# Sheet2.net
KiCad netlist of a schematic drawn in Altium Designer
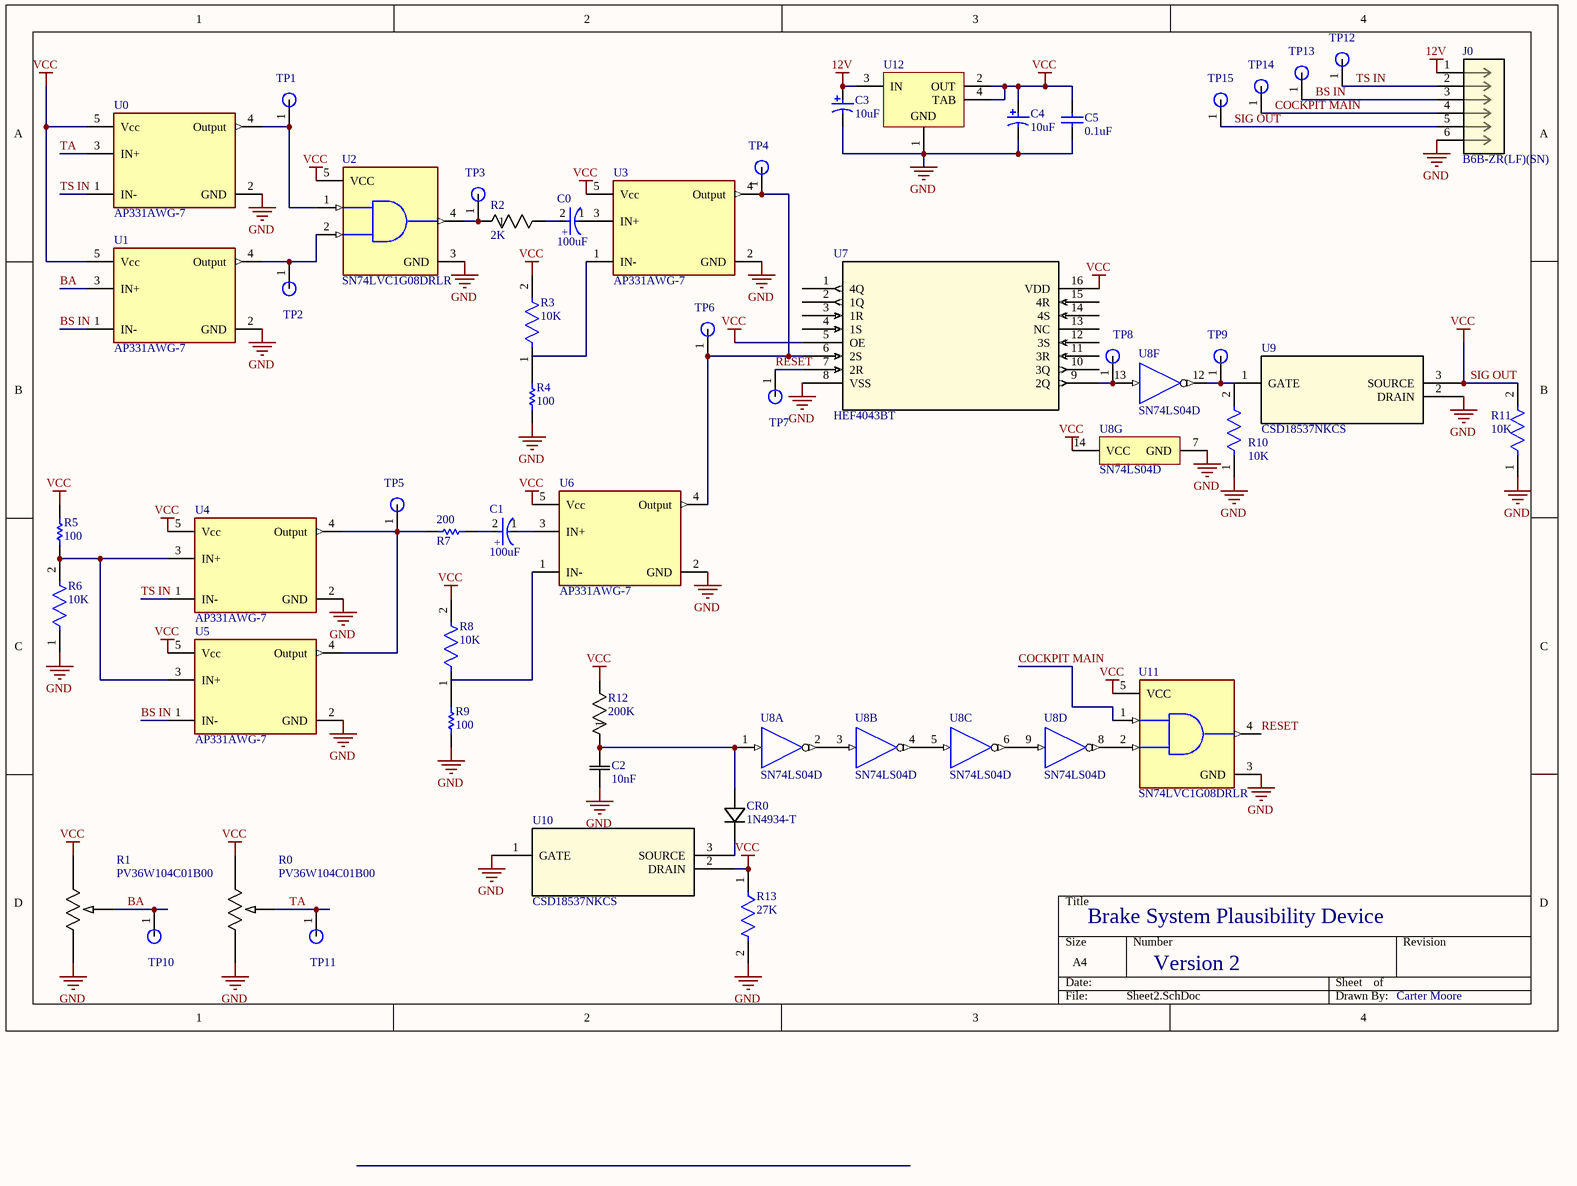
[diagram p0: Sheet2.SchDoc]

(export (version "E")
  (design (tool "Eeschema 10.0.6"))
  (components
    (comp (ref "200")
      (value "R7")
      (footprint "RESC0603X28X15ML05T05")
      (fields (field (name "MANUFACTURER") "Vishay Dale") (field (name "PART NUMBER") "CRCW0201200RJNED"))
      (libsource (lib "Schlib2") (part "RES"))
    )
    (comp (ref "C0")
      (value "100uF")
      (footprint "FP-MAL2150-1010-MFG")
      (description "CAP ALUM 100UF 20% 50V SMD")
      (fields (field (name "TOLERANCE") "20%"))
      (libsource (lib "Schlib2") (part "203bc49f2ac43e59fd269a8c329ed05"))
    )
    (comp (ref "C1")
      (value "100uF")
      (footprint "FP-MAL2150-1010-MFG")
      (description "CAP ALUM 100UF 20% 50V SMD")
      (fields (field (name "TOLERANCE") "20%"))
      (libsource (lib "Schlib2") (part "203bc49f2ac43e59fd269a8c329ed05"))
    )
    (comp (ref "C2")
      (value "10nF")
      (footprint "CAP_C317C_MR_X7R_KEM")
      (description "CAP CER 10000PF 50V X7R RADIAL")
      (fields
        (field (name "MANUFACTURER_PART_NUMBER") "C317C103K5R5TA")
        (field (name "COPYRIGHT") "Copyright (C) 2023 Ultra Librarian. All rights reserved.")
      )
      (libsource (lib "Schlib2") (part "C317C103K5R5TA"))
    )
    (comp (ref "C3")
      (value "10uF")
      (footprint "PNSC-EEU-EE2G100-2_V")
      (fields (field (name "PARTNUMBER") "EEU-EE2G100") (field (name "MANUFACTURER") "Panasonic"))
      (libsource (lib "Altium Content Vault") (part "PNSC-CAP-P-2"))
    )
    (comp (ref "C4")
      (value "10uF")
      (footprint "PNSC-EEU-EE2G100-2_V")
      (fields (field (name "PARTNUMBER") "EEU-EE2G100") (field (name "MANUFACTURER") "Panasonic"))
      (libsource (lib "Altium Content Vault") (part "PNSC-CAP-P-2"))
    )
    (comp (ref "C5")
      (value "0.1uF")
      (footprint "AVX-SA115C104KAR")
      (fields (field (name "TOLERANCE") "±10%") (field (name "MANUFACTURER") "AVX"))
      (libsource (lib "Altium Content Vault") (part "CAP-NP-2"))
    )
    (comp (ref "CR0")
      (value "1N4934-T")
      (footprint "DO-41_DIO")
      (description "No Description Available")
      (fields (field (name "COPYRIGHT") "Copyright (C) 2023 Ultra Librarian. All rights reserved."))
      (libsource (lib "Schlib2") (part "1N4934-T"))
    )
    (comp (ref "J0")
      (value "B6B-ZR(LF)(SN)")
      (footprint "CONN_B6B-ZR_JST")
      (description "CONN HEADER VERT 6POS 1.5MM")
      (fields (field (name "COPYRIGHT") "Copyright (C) 2023 Ultra Librarian. All rights reserved."))
      (libsource (lib "Schlib2") (part "B6B-ZRLFSN"))
    )
    (comp (ref "R0")
      (value "PV36W104C01B00")
      (footprint "POT_PV36W_BRN")
      (description "TRIMMER 100K OHM 0.5W PC PIN TOP")
      (libsource (lib "Schlib2") (part "PV36W104C01B00"))
    )
    (comp (ref "R1")
      (value "PV36W104C01B00")
      (footprint "POT_PV36W_BRN")
      (description "TRIMMER 100K OHM 0.5W PC PIN TOP")
      (libsource (lib "Schlib2") (part "PV36W104C01B00"))
    )
    (comp (ref "R2")
      (value "2K")
      (footprint "YAG_MF25_YAG")
      (description "No Description Available")
      (fields
        (field (name "MANUFACTURER_PART_NUMBER") "MFR-25FRF52-2K")
        (field (name "COPYRIGHT") "Copyright (C) 2023 Ultra Librarian. All rights reserved.")
      )
      (libsource (lib "Schlib2") (part "MFR-25FRF52-2K"))
    )
    (comp (ref "R3")
      (value "10K")
      (footprint "FP-MF0207-MFG")
      (description "RES 10K OHM 1% 0.6W AXIAL")
      (fields (field (name "TOLERANCE") "1%"))
      (libsource (lib "Altium Content Vault") (part "1029c3af85768c4190bb7ad29bc67b5"))
    )
    (comp (ref "R4")
      (value "100")
      (footprint "RESA60-630X240")
      (description "Axial Resistor, 100 Ohm, +/- 1%, 0.25 W, -55 to 155 degC, 2-Pin THD, RoHS, Bulk")
      (fields (field (name "TOLERANCE") "1%"))
      (libsource (lib "Altium Content Vault") (part "RES-2"))
    )
    (comp (ref "R5")
      (value "100")
      (footprint "RESA60-630X240")
      (description "Axial Resistor, 100 Ohm, +/- 1%, 0.25 W, -55 to 155 degC, 2-Pin THD, RoHS, Bulk")
      (fields (field (name "TOLERANCE") "1%"))
      (libsource (lib "Schlib2") (part "RES-2"))
    )
    (comp (ref "R6")
      (value "10K")
      (footprint "FP-MF0207-MFG")
      (description "RES 10K OHM 1% 0.6W AXIAL")
      (fields (field (name "TOLERANCE") "1%"))
      (libsource (lib "Schlib2") (part "1029c3af85768c4190bb7ad29bc67b5"))
    )
    (comp (ref "R8")
      (value "10K")
      (footprint "FP-MF0207-MFG")
      (description "RES 10K OHM 1% 0.6W AXIAL")
      (fields (field (name "TOLERANCE") "1%"))
      (libsource (lib "Altium Content Vault") (part "1029c3af85768c4190bb7ad29bc67b5"))
    )
    (comp (ref "R9")
      (value "100")
      (footprint "RESA60-630X240")
      (description "Axial Resistor, 100 Ohm, +/- 1%, 0.25 W, -55 to 155 degC, 2-Pin THD, RoHS, Bulk")
      (fields (field (name "TOLERANCE") "1%"))
      (libsource (lib "Altium Content Vault") (part "RES-2"))
    )
    (comp (ref "R10")
      (value "10K")
      (footprint "FP-MF0207-MFG")
      (description "RES 10K OHM 1% 0.6W AXIAL")
      (fields (field (name "TOLERANCE") "1%"))
      (libsource (lib "Schlib2") (part "1029c3af85768c4190bb7ad29bc67b5"))
    )
    (comp (ref "R11")
      (value "10K")
      (footprint "FP-MF0207-MFG")
      (description "RES 10K OHM 1% 0.6W AXIAL")
      (fields (field (name "TOLERANCE") "1%"))
      (libsource (lib "Schlib2") (part "1029c3af85768c4190bb7ad29bc67b5"))
    )
    (comp (ref "R12")
      (value "200K")
      (footprint "YAG_MF25_YAG")
      (description "RES 200K OHM 1% 1/4W AXIAL")
      (fields
        (field (name "MANUFACTURER_PART_NUMBER") "MFR-25FRF52-200K")
        (field (name "COPYRIGHT") "Copyright (C) 2023 Ultra Librarian. All rights reserved.")
      )
      (libsource (lib "Schlib2") (part "MFR-25FRF52-200K"))
    )
    (comp (ref "R13")
      (value "27K")
      (footprint "FP-RT0402-MFG")
      (description "RES SMD 27K OHM 0.5% 1/16W 0402")
      (fields
        (field (name "MANUFACTURER") "Yageo")
        (field (name "MANUFACTURER PART NUMBER") "RT0402DRE0727KL")
      )
      (libsource (lib "Altium Content Vault") (part "1029c3af85768c4190bb7ad29bc67b5"))
    )
    (comp (ref "TP1") (value "Test Point") (footprint "TP1") (libsource (lib "Schlib2") (part "Test Point")))
    (comp (ref "TP2") (value "Test Point") (footprint "TP1") (libsource (lib "Schlib2") (part "Test Point")))
    (comp (ref "TP3") (value "Test Point") (footprint "TP1") (libsource (lib "Schlib2") (part "Test Point")))
    (comp (ref "TP4") (value "Test Point") (footprint "TP1") (libsource (lib "Schlib2") (part "Test Point")))
    (comp (ref "TP5") (value "Test Point") (footprint "TP1") (libsource (lib "Schlib2") (part "Test Point")))
    (comp (ref "TP6") (value "Test Point") (footprint "TP1") (libsource (lib "Schlib2") (part "Test Point")))
    (comp (ref "TP7") (value "Test Point") (footprint "TP1") (libsource (lib "Schlib2") (part "Test Point")))
    (comp (ref "TP8") (value "Test Point") (footprint "TP1") (libsource (lib "Schlib2") (part "Test Point")))
    (comp (ref "TP9") (value "Test Point") (footprint "TP1") (libsource (lib "Schlib2") (part "Test Point")))
    (comp (ref "TP10") (value "Test Point") (footprint "TP1") (libsource (lib "Schlib2") (part "Test Point")))
    (comp (ref "TP11") (value "Test Point") (footprint "TP1") (libsource (lib "Schlib2") (part "Test Point")))
    (comp (ref "TP12") (value "Test Point") (footprint "TP1") (libsource (lib "Schlib2") (part "Test Point")))
    (comp (ref "TP13") (value "Test Point") (footprint "TP1") (libsource (lib "Schlib2") (part "Test Point")))
    (comp (ref "TP14") (value "Test Point") (footprint "TP1") (libsource (lib "Schlib2") (part "Test Point")))
    (comp (ref "TP15") (value "Test Point") (footprint "TP1") (libsource (lib "Schlib2") (part "Test Point")))
    (comp (ref "U0")
      (value "AP331AWG-7")
      (footprint "FP-SOT25-MFG")
      (description "IC COMPARATOR SGL DIFF SOT-25")
      (fields
        (field (name "MANUFACTURER") "Diodes Inc.")
        (field (name "OCTOPART") "https://octopart.com/ap331awg-7-diodes+inc.-12688108")
      )
      (libsource (lib "Schlib2") (part "84157f6d693ce6938d681314262b7f3"))
    )
    (comp (ref "U1")
      (value "AP331AWG-7")
      (footprint "FP-SOT25-MFG")
      (description "IC COMPARATOR SGL DIFF SOT-25")
      (fields
        (field (name "MANUFACTURER") "Diodes Inc.")
        (field (name "OCTOPART") "https://octopart.com/ap331awg-7-diodes+inc.-12688108")
      )
      (libsource (lib "Schlib2") (part "84157f6d693ce6938d681314262b7f3"))
    )
    (comp (ref "U2")
      (value "SN74LVC1G08DRLR")
      (footprint "FP-DRL0005A-MFG")
      (description "IC GATE AND 1CH 2-INP SOT5")
      (fields
        (field (name "MANUFACTURER") "Texas Instruments")
        (field (name "OCTOPART") "https://octopart.com/sn74lvc1g08drlr-texas+instruments-464956")
      )
      (libsource (lib "Schlib2") (part "cbd873ac6525a059c6951788f409ef0"))
    )
    (comp (ref "U3")
      (value "AP331AWG-7")
      (footprint "FP-SOT25-MFG")
      (description "IC COMPARATOR SGL DIFF SOT-25")
      (fields
        (field (name "MANUFACTURER") "Diodes Inc.")
        (field (name "OCTOPART") "https://octopart.com/ap331awg-7-diodes+inc.-12688108")
      )
      (libsource (lib "Schlib2") (part "84157f6d693ce6938d681314262b7f3"))
    )
    (comp (ref "U4")
      (value "AP331AWG-7")
      (footprint "FP-SOT25-MFG")
      (description "IC COMPARATOR SGL DIFF SOT-25")
      (fields
        (field (name "MANUFACTURER") "Diodes Inc.")
        (field (name "OCTOPART") "https://octopart.com/ap331awg-7-diodes+inc.-12688108")
      )
      (libsource (lib "Schlib2") (part "84157f6d693ce6938d681314262b7f3"))
    )
    (comp (ref "U5")
      (value "AP331AWG-7")
      (footprint "FP-SOT25-MFG")
      (description "IC COMPARATOR SGL DIFF SOT-25")
      (fields
        (field (name "MANUFACTURER") "Diodes Inc.")
        (field (name "OCTOPART") "https://octopart.com/ap331awg-7-diodes+inc.-12688108")
      )
      (libsource (lib "Schlib2") (part "84157f6d693ce6938d681314262b7f3"))
    )
    (comp (ref "U6")
      (value "AP331AWG-7")
      (footprint "FP-SOT25-MFG")
      (description "IC COMPARATOR SGL DIFF SOT-25")
      (fields
        (field (name "MANUFACTURER") "Diodes Inc.")
        (field (name "OCTOPART") "https://octopart.com/ap331awg-7-diodes+inc.-12688108")
      )
      (libsource (lib "Schlib2") (part "84157f6d693ce6938d681314262b7f3"))
    )
    (comp (ref "U7")
      (value "HEF4043BT")
      (footprint "SOT109-1_NXP")
      (description "IC R/S LATCH 3-STATE QUAD 16SOIC")
      (fields (field (name "COPYRIGHT") "Copyright (C) 2023 Ultra Librarian. All rights reserved."))
      (libsource (lib "Schlib2") (part "HEF4043BT"))
    )
    (comp (ref "U8")
      (value "SN74LS04D")
      (footprint "D0014A_N")
      (description "Hex inverters, D0014A, TUBE")
      (fields
        (field (name "GENERIC PART NUMBER") "SN74LS04")
        (field (name "MANUFACTURER") "Texas Instruments")
      )
      (libsource (lib "Schlib2") (part "TI-CD_SNX4XXXXXX4X_19A-14"))
    )
    (comp (ref "U9")
      (value "CSD18537NKCS")
      (footprint "KCS3_TEX")
      (description "No Description Available")
      (fields (field (name "COPYRIGHT") "Copyright (C) 2023 Ultra Librarian. All rights reserved."))
      (libsource (lib "Schlib2") (part "CSD18537NKCS"))
    )
    (comp (ref "U10")
      (value "CSD18537NKCS")
      (footprint "KCS3_TEX")
      (description "No Description Available")
      (fields (field (name "COPYRIGHT") "Copyright (C) 2023 Ultra Librarian. All rights reserved."))
      (libsource (lib "Schlib2") (part "CSD18537NKCS"))
    )
    (comp (ref "U11")
      (value "SN74LVC1G08DRLR")
      (footprint "FP-DRL0005A-MFG")
      (description "IC GATE AND 1CH 2-INP SOT5")
      (fields
        (field (name "MANUFACTURER") "Texas Instruments")
        (field (name "OCTOPART") "https://octopart.com/sn74lvc1g08drlr-texas+instruments-464956")
      )
      (libsource (lib "Schlib2") (part "cbd873ac6525a059c6951788f409ef0"))
    )
    (comp (ref "U12")
      (value "LM1117MPX-5.0/NOPB")
      (footprint "DCY0004A_L")
      (description "800mA Low-Dropout Linear Regulator, 4-pin SOT-223, Pb-Free")
      (fields (field (name "MANUFACTURER") "Texas Instruments"))
      (libsource (lib "Altium Content Vault") (part "PM-REG-LM1086-SOT4"))
    )
  )
  (nets
    (net (code "1") (name "/BA") (class "Default")
      (node (ref "R1") (pin "2") (pinfunction "2_2") (pintype "passive"))
      (node (ref "TP10") (pin "1") (pinfunction "1_1") (pintype "passive"))
      (node (ref "U1") (pin "3") (pinfunction "IN+_3") (pintype "tri_state"))
    )
    (net (code "2") (name "/BS IN") (class "Default")
      (node (ref "J0") (pin "3") (pinfunction "3_3") (pintype "passive"))
      (node (ref "TP13") (pin "1") (pinfunction "1_1") (pintype "passive"))
      (node (ref "U1") (pin "1") (pinfunction "IN-_1") (pintype "tri_state"))
      (node (ref "U5") (pin "1") (pinfunction "IN-_1") (pintype "tri_state"))
    )
    (net (code "3") (name "/COCKPIT MAIN") (class "Default")
      (node (ref "J0") (pin "4") (pinfunction "4_4") (pintype "passive"))
      (node (ref "TP14") (pin "1") (pinfunction "1_1") (pintype "passive"))
      (node (ref "U11") (pin "1") (pinfunction "A_1") (pintype "input"))
    )
    (net (code "4") (name "/RESET") (class "Default")
      (node (ref "TP7") (pin "1") (pinfunction "1_1") (pintype "passive"))
      (node (ref "U11") (pin "4") (pinfunction "Y_4") (pintype "output"))
      (node (ref "U7") (pin "7") (pinfunction "2R_7") (pintype "input"))
    )
    (net (code "5") (name "/TA") (class "Default")
      (node (ref "R0") (pin "2") (pinfunction "2_2") (pintype "passive"))
      (node (ref "TP11") (pin "1") (pinfunction "1_1") (pintype "passive"))
      (node (ref "U0") (pin "3") (pinfunction "IN+_3") (pintype "tri_state"))
    )
    (net (code "6") (name "/TS IN") (class "Default")
      (node (ref "J0") (pin "2") (pinfunction "2_2") (pintype "passive"))
      (node (ref "TP12") (pin "1") (pinfunction "1_1") (pintype "passive"))
      (node (ref "U0") (pin "1") (pinfunction "IN-_1") (pintype "tri_state"))
      (node (ref "U4") (pin "1") (pinfunction "IN-_1") (pintype "tri_state"))
    )
    (net (code "7") (name "12V") (class "Default")
      (node (ref "C3") (pin "1") (pinfunction "1_1") (pintype "passive"))
      (node (ref "J0") (pin "1") (pinfunction "1_1") (pintype "passive"))
      (node (ref "U12") (pin "3") (pinfunction "IN_3") (pintype "power_in"))
    )
    (net (code "8") (name "GND") (class "Default")
      (node (ref "C2") (pin "1") (pinfunction "1_1") (pintype "passive"))
      (node (ref "C3") (pin "2") (pinfunction "2_2") (pintype "passive"))
      (node (ref "C4") (pin "2") (pinfunction "2_2") (pintype "passive"))
      (node (ref "C5") (pin "1") (pinfunction "1_1") (pintype "passive"))
      (node (ref "J0") (pin "6") (pinfunction "6_6") (pintype "passive"))
      (node (ref "R0") (pin "3") (pinfunction "3_3") (pintype "passive"))
      (node (ref "R1") (pin "3") (pinfunction "3_3") (pintype "passive"))
      (node (ref "R10") (pin "1") (pinfunction "1_1") (pintype "passive"))
      (node (ref "R11") (pin "1") (pinfunction "1_1") (pintype "passive"))
      (node (ref "R13") (pin "2") (pinfunction "2_2") (pintype "passive"))
      (node (ref "R4") (pin "1") (pinfunction "1_1") (pintype "passive"))
      (node (ref "R6") (pin "1") (pinfunction "1_1") (pintype "passive"))
      (node (ref "R9") (pin "1") (pinfunction "1_1") (pintype "passive"))
      (node (ref "U0") (pin "2") (pinfunction "GND_2") (pintype "power_in"))
      (node (ref "U1") (pin "2") (pinfunction "GND_2") (pintype "power_in"))
      (node (ref "U10") (pin "1") (pinfunction "GATE_1") (pintype "passive"))
      (node (ref "U11") (pin "3") (pinfunction "GND_3") (pintype "power_in"))
      (node (ref "U12") (pin "1") (pinfunction "GND_1") (pintype "power_in"))
      (node (ref "U2") (pin "3") (pinfunction "GND_3") (pintype "power_in"))
      (node (ref "U3") (pin "2") (pinfunction "GND_2") (pintype "power_in"))
      (node (ref "U4") (pin "2") (pinfunction "GND_2") (pintype "power_in"))
      (node (ref "U5") (pin "2") (pinfunction "GND_2") (pintype "power_in"))
      (node (ref "U6") (pin "2") (pinfunction "GND_2") (pintype "power_in"))
      (node (ref "U7") (pin "8") (pinfunction "VSS_8") (pintype "power_in"))
      (node (ref "U8") (pin "7") (pinfunction "GND_7") (pintype "power_in"))
      (node (ref "U9") (pin "2") (pinfunction "DRAIN_2") (pintype "passive"))
    )
    (net (code "9") (name "Net-(C0-A)") (class "Default")
      (node (ref "C0") (pin "2") (pinfunction "A_2") (pintype "passive"))
      (node (ref "R2") (pin "2") (pinfunction "2_2") (pintype "passive"))
    )
    (net (code "10") (name "Net-(C0-C)") (class "Default")
      (node (ref "C0") (pin "1") (pinfunction "C_1") (pintype "passive"))
      (node (ref "U3") (pin "3") (pinfunction "IN+_3") (pintype "tri_state"))
    )
    (net (code "11") (name "Net-(C1-A)") (class "Default")
      (node (ref "200") (pin "2") (pinfunction "2_2") (pintype "passive"))
      (node (ref "C1") (pin "2") (pinfunction "A_2") (pintype "passive"))
    )
    (net (code "12") (name "Net-(C1-C)") (class "Default")
      (node (ref "C1") (pin "1") (pinfunction "C_1") (pintype "passive"))
      (node (ref "U6") (pin "3") (pinfunction "IN+_3") (pintype "tri_state"))
    )
    (net (code "13") (name "Net-(R3-Pad1)") (class "Default")
      (node (ref "R3") (pin "1") (pinfunction "1_1") (pintype "passive"))
      (node (ref "R4") (pin "2") (pinfunction "2_2") (pintype "passive"))
    )
    (net (code "14") (name "Net-(R8-Pad1)") (class "Default")
      (node (ref "R8") (pin "1") (pinfunction "1_1") (pintype "passive"))
      (node (ref "R9") (pin "2") (pinfunction "2_2") (pintype "passive"))
    )
    (net (code "15") (name "Net-(U0-Output)") (class "Default")
      (node (ref "TP1") (pin "1") (pinfunction "1_1") (pintype "passive"))
      (node (ref "U0") (pin "4") (pinfunction "Output_4") (pintype "output"))
      (node (ref "U2") (pin "1") (pinfunction "A_1") (pintype "input"))
    )
    (net (code "16") (name "Net-(U1-Output)") (class "Default")
      (node (ref "TP2") (pin "1") (pinfunction "1_1") (pintype "passive"))
      (node (ref "U1") (pin "4") (pinfunction "Output_4") (pintype "output"))
      (node (ref "U2") (pin "2") (pinfunction "B_2") (pintype "input"))
    )
    (net (code "17") (name "Net-(U2-Y)") (class "Default")
      (node (ref "R2") (pin "1") (pinfunction "1_1") (pintype "passive"))
      (node (ref "TP3") (pin "1") (pinfunction "1_1") (pintype "passive"))
      (node (ref "U2") (pin "4") (pinfunction "Y_4") (pintype "output"))
    )
    (net (code "18") (name "Net-(U3-Output)") (class "Default")
      (node (ref "TP4") (pin "1") (pinfunction "1_1") (pintype "passive"))
      (node (ref "TP6") (pin "1") (pinfunction "1_1") (pintype "passive"))
      (node (ref "U3") (pin "4") (pinfunction "Output_4") (pintype "output"))
      (node (ref "U6") (pin "4") (pinfunction "Output_4") (pintype "output"))
      (node (ref "U7") (pin "6") (pinfunction "2S_6") (pintype "input"))
    )
    (net (code "19") (name "Net-(U4-IN+)") (class "Default")
      (node (ref "R5") (pin "1") (pinfunction "1_1") (pintype "passive"))
      (node (ref "R6") (pin "2") (pinfunction "2_2") (pintype "passive"))
      (node (ref "U4") (pin "3") (pinfunction "IN+_3") (pintype "tri_state"))
      (node (ref "U5") (pin "3") (pinfunction "IN+_3") (pintype "tri_state"))
    )
    (net (code "20") (name "Net-(U4-Output)") (class "Default")
      (node (ref "200") (pin "1") (pinfunction "1_1") (pintype "passive"))
      (node (ref "TP5") (pin "1") (pinfunction "1_1") (pintype "passive"))
      (node (ref "U4") (pin "4") (pinfunction "Output_4") (pintype "output"))
      (node (ref "U5") (pin "4") (pinfunction "Output_4") (pintype "output"))
    )
    (net (code "21") (name "Net-(U7-2Q)") (class "Default")
      (node (ref "TP8") (pin "1") (pinfunction "1_1") (pintype "passive"))
      (node (ref "U7") (pin "9") (pinfunction "2Q_9") (pintype "output"))
      (node (ref "U8") (pin "13") (pinfunction "6A_13") (pintype "input"))
    )
    (net (code "22") (name "Net-(U8A-1A)") (class "Default")
      (node (ref "C2") (pin "2") (pinfunction "2_2") (pintype "passive"))
      (node (ref "CR0") (pin "2") (pinfunction "2_2") (pintype "passive"))
      (node (ref "R12") (pin "1") (pinfunction "1_1") (pintype "passive"))
      (node (ref "U8") (pin "1") (pinfunction "1A_1") (pintype "input"))
    )
    (net (code "23") (name "Net-(U8A-~{1Y})") (class "Default")
      (node (ref "U8") (pin "2") (pinfunction "~{1Y}_2") (pintype "output"))
      (node (ref "U8") (pin "3") (pinfunction "2A_3") (pintype "input"))
    )
    (net (code "24") (name "Net-(U8B-~{2Y})") (class "Default")
      (node (ref "U8") (pin "4") (pinfunction "~{2Y}_4") (pintype "output"))
      (node (ref "U8") (pin "5") (pinfunction "3A_5") (pintype "input"))
    )
    (net (code "25") (name "Net-(U8C-~{3Y})") (class "Default")
      (node (ref "U8") (pin "6") (pinfunction "~{3Y}_6") (pintype "output"))
      (node (ref "U8") (pin "9") (pinfunction "4A_9") (pintype "input"))
    )
    (net (code "26") (name "Net-(U8F-~{6Y})") (class "Default")
      (node (ref "R10") (pin "2") (pinfunction "2_2") (pintype "passive"))
      (node (ref "TP9") (pin "1") (pinfunction "1_1") (pintype "passive"))
      (node (ref "U8") (pin "12") (pinfunction "~{6Y}_12") (pintype "output"))
      (node (ref "U9") (pin "1") (pinfunction "GATE_1") (pintype "passive"))
    )
    (net (code "27") (name "Net-(U10-SOURCE)") (class "Default")
      (node (ref "CR0") (pin "1") (pinfunction "1_1") (pintype "passive"))
      (node (ref "U10") (pin "3") (pinfunction "SOURCE_3") (pintype "passive"))
    )
    (net (code "28") (name "Net-(U11-B)") (class "Default")
      (node (ref "U11") (pin "2") (pinfunction "B_2") (pintype "input"))
      (node (ref "U8") (pin "8") (pinfunction "~{4Y}_8") (pintype "output"))
    )
    (net (code "29") (name "VCC") (class "Default")
      (node (ref "C4") (pin "1") (pinfunction "1_1") (pintype "passive"))
      (node (ref "C5") (pin "2") (pinfunction "2_2") (pintype "passive"))
      (node (ref "J0") (pin "5") (pinfunction "5_5") (pintype "passive"))
      (node (ref "R0") (pin "1") (pinfunction "1_1") (pintype "passive"))
      (node (ref "R1") (pin "1") (pinfunction "1_1") (pintype "passive"))
      (node (ref "R11") (pin "2") (pinfunction "2_2") (pintype "passive"))
      (node (ref "R12") (pin "2") (pinfunction "2_2") (pintype "passive"))
      (node (ref "R13") (pin "1") (pinfunction "1_1") (pintype "passive"))
      (node (ref "R3") (pin "2") (pinfunction "2_2") (pintype "passive"))
      (node (ref "R5") (pin "2") (pinfunction "2_2") (pintype "passive"))
      (node (ref "R8") (pin "2") (pinfunction "2_2") (pintype "passive"))
      (node (ref "TP15") (pin "1") (pinfunction "1_1") (pintype "passive"))
      (node (ref "U0") (pin "5") (pinfunction "Vcc_5") (pintype "power_in"))
      (node (ref "U1") (pin "5") (pinfunction "Vcc_5") (pintype "power_in"))
      (node (ref "U10") (pin "2") (pinfunction "DRAIN_2") (pintype "passive"))
      (node (ref "U11") (pin "5") (pinfunction "VCC_5") (pintype "power_in"))
      (node (ref "U12") (pin "2") (pinfunction "OUT_2") (pintype "power_in"))
      (node (ref "U12") (pin "4") (pinfunction "TAB_4") (pintype "power_in"))
      (node (ref "U2") (pin "5") (pinfunction "VCC_5") (pintype "power_in"))
      (node (ref "U3") (pin "5") (pinfunction "Vcc_5") (pintype "power_in"))
      (node (ref "U4") (pin "5") (pinfunction "Vcc_5") (pintype "power_in"))
      (node (ref "U5") (pin "5") (pinfunction "Vcc_5") (pintype "power_in"))
      (node (ref "U6") (pin "5") (pinfunction "Vcc_5") (pintype "power_in"))
      (node (ref "U7") (pin "16") (pinfunction "VDD_16") (pintype "power_in"))
      (node (ref "U7") (pin "5") (pinfunction "OE_5") (pintype "passive"))
      (node (ref "U8") (pin "14") (pinfunction "VCC_14") (pintype "power_in"))
      (node (ref "U9") (pin "3") (pinfunction "SOURCE_3") (pintype "passive"))
    )
    (net (code "30") (name "unconnected-(U3-IN--Pad1)") (class "Default")
      (node (ref "U3") (pin "1") (pinfunction "IN-_1") (pintype "tri_state"))
    )
    (net (code "31") (name "unconnected-(U6-IN--Pad1)") (class "Default")
      (node (ref "U6") (pin "1") (pinfunction "IN-_1") (pintype "tri_state"))
    )
    (net (code "32") (name "unconnected-(U7-1Q-Pad2)") (class "Default")
      (node (ref "U7") (pin "2") (pinfunction "1Q_2") (pintype "output"))
    )
    (net (code "33") (name "unconnected-(U7-1R-Pad3)") (class "Default")
      (node (ref "U7") (pin "3") (pinfunction "1R_3") (pintype "input"))
    )
    (net (code "34") (name "unconnected-(U7-1S-Pad4)") (class "Default")
      (node (ref "U7") (pin "4") (pinfunction "1S_4") (pintype "input"))
    )
    (net (code "35") (name "unconnected-(U7-3Q-Pad10)") (class "Default")
      (node (ref "U7") (pin "10") (pinfunction "3Q_10") (pintype "output"))
    )
    (net (code "36") (name "unconnected-(U7-3R-Pad11)") (class "Default")
      (node (ref "U7") (pin "11") (pinfunction "3R_11") (pintype "input"))
    )
    (net (code "37") (name "unconnected-(U7-3S-Pad12)") (class "Default")
      (node (ref "U7") (pin "12") (pinfunction "3S_12") (pintype "input"))
    )
    (net (code "38") (name "unconnected-(U7-4Q-Pad1)") (class "Default")
      (node (ref "U7") (pin "1") (pinfunction "4Q_1") (pintype "output"))
    )
    (net (code "39") (name "unconnected-(U7-4R-Pad15)") (class "Default")
      (node (ref "U7") (pin "15") (pinfunction "4R_15") (pintype "input"))
    )
    (net (code "40") (name "unconnected-(U7-4S-Pad14)") (class "Default")
      (node (ref "U7") (pin "14") (pinfunction "4S_14") (pintype "input"))
    )
    (net (code "41") (name "unconnected-(U7-NC-Pad13)") (class "Default")
      (node (ref "U7") (pin "13") (pinfunction "NC_13") (pintype "passive"))
    )
  )
)
